# Mainboard.net
KiCad netlist of a schematic drawn in Altium Designer
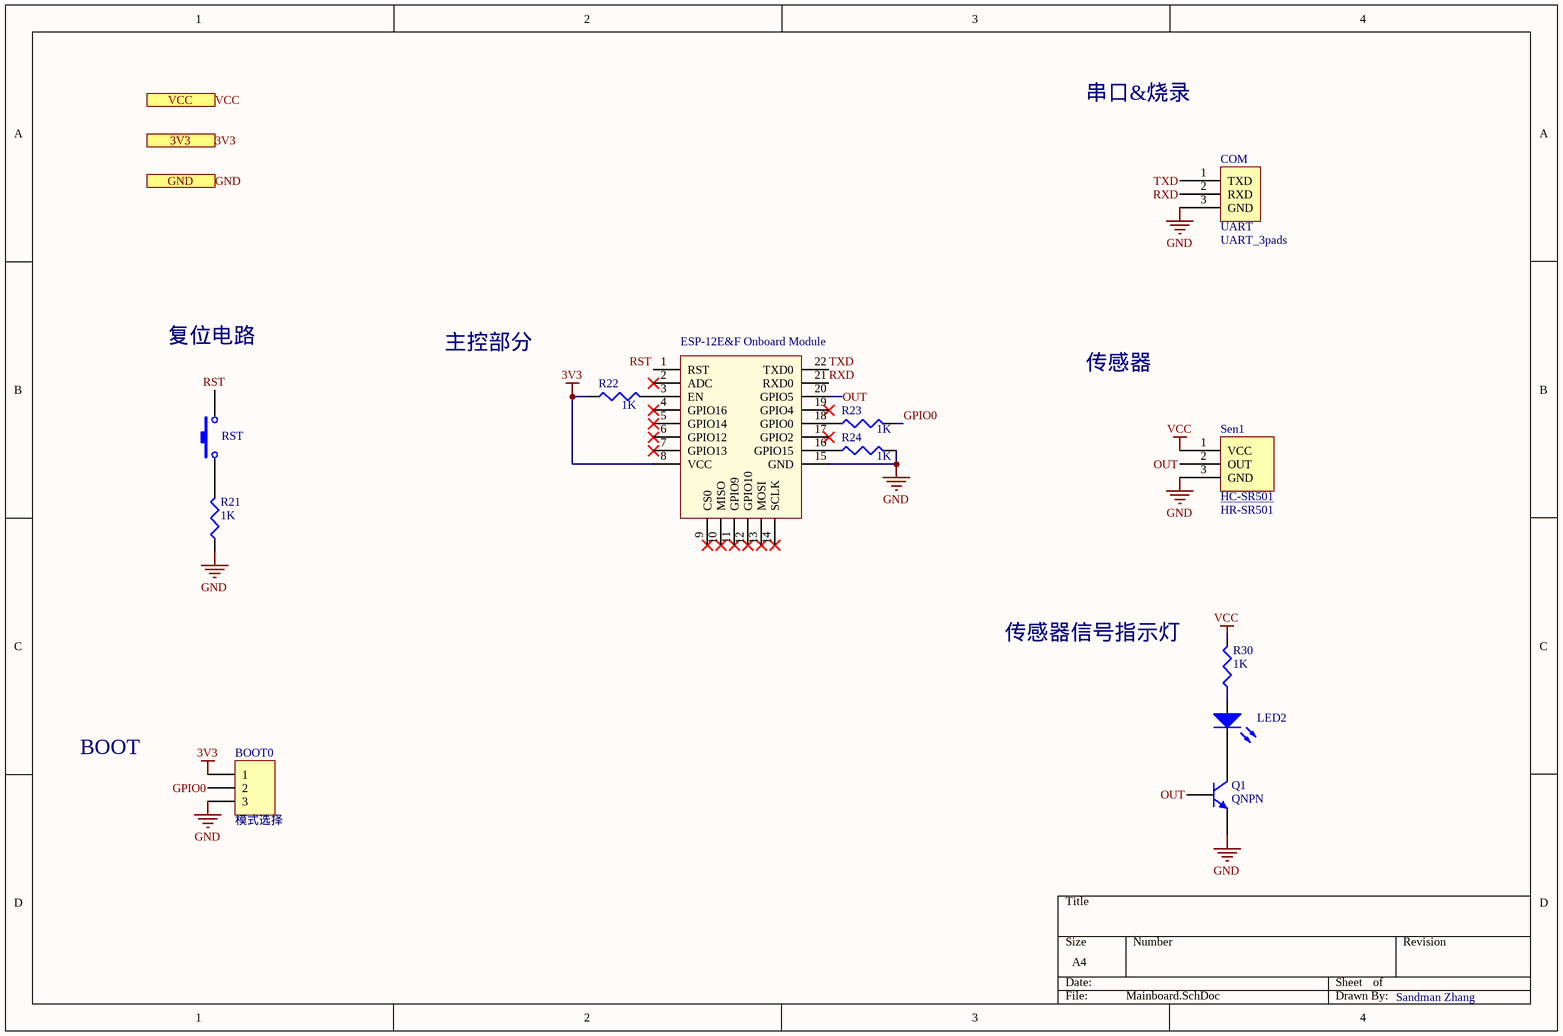
[diagram p0: Mainboard.SchDoc]

(export (version "E")
  (design (tool "Eeschema 10.0.6"))
  (components
    (comp (ref "BOOT0")
      (value "模式选择")
      (footprint "HDR1X3")
      (description "Header, 3-Pin")
      (fields (field (name "PUBLISHER") "Altium Limited"))
      (libsource (lib "Miscellaneous Connectors") (part "Header 3"))
    )
    (comp (ref "COM")
      (value "UART_3pads")
      (footprint "3pads")
      (libsource (lib "Connectivity_pads") (part "UART_3pads"))
    )
    (comp (ref "LED2")
      (value "LED3")
      (footprint "Miscellaneous Devices:6-0805_N")
      (description "Typical BLUE SiC LED")
      (fields (field (name "PUBLISHER") "Altium Limited"))
      (libsource (lib "Miscellaneous Devices") (part "LED3"))
    )
    (comp (ref "Q1")
      (value "QNPN")
      (footprint "SOT-23B_N")
      (description "NPN Bipolar Transistor")
      (fields (field (name "PUBLISHER") "Altium Limited"))
      (libsource (lib "Miscellaneous Devices") (part "QNPN"))
    )
    (comp (ref "R21")
      (value "1K")
      (footprint "J1-0603")
      (description "Resistor")
      (fields (field (name "Comment") "Res3") (field (name "PUBLISHER") "Altium Limited"))
      (libsource (lib "Miscellaneous Devices") (part "Res3"))
    )
    (comp (ref "R22")
      (value "1K")
      (footprint "J1-0603")
      (description "Resistor")
      (fields (field (name "Comment") "Res3") (field (name "PUBLISHER") "Altium Limited"))
      (libsource (lib "Miscellaneous Devices") (part "Res3"))
    )
    (comp (ref "R23")
      (value "1K")
      (footprint "J1-0603")
      (description "Resistor")
      (fields (field (name "Comment") "Res3") (field (name "PUBLISHER") "Altium Limited"))
      (libsource (lib "Miscellaneous Devices") (part "Res3"))
    )
    (comp (ref "R24")
      (value "1K")
      (footprint "J1-0603")
      (description "Resistor")
      (fields (field (name "Comment") "Res3") (field (name "PUBLISHER") "Altium Limited"))
      (libsource (lib "Miscellaneous Devices") (part "Res3"))
    )
    (comp (ref "R30")
      (value "1K")
      (footprint "6-0805_N")
      (description "Resistor")
      (fields (field (name "Comment") "Res3") (field (name "PUBLISHER") "Altium Limited"))
      (libsource (lib "Miscellaneous Devices") (part "Res3"))
    )
    (comp (ref "RST")
      (value "SW-PB")
      (footprint "SPST-2")
      (description "Switch")
      (fields (field (name "PUBLISHER") "Altium Limited"))
      (libsource (lib "Miscellaneous Devices") (part "SW-PB"))
    )
    (comp (ref "Sen1")
      (value "HR-SR501")
      (footprint "HR-SR501")
      (description "人体红外感应模块")
      (libsource (lib "Common_Modules") (part "HR-SR501"))
    )
    (comp (ref "U1")
      (value "ESP-12E&F Onboard Module")
      (footprint "ESP-12E&F Module")
      (libsource (lib "ESP-12E&F Onboard Module") (part "ESP-12E&F Onboard Module"))
    )
  )
  (nets
    (net (code "1") (name "/GPIO0") (class "Default")
      (node (ref "BOOT0") (pin "2") (pinfunction "2_2") (pintype "passive"))
      (node (ref "R23") (pin "2") (pinfunction "2_2") (pintype "passive"))
    )
    (net (code "2") (name "/OUT") (class "Default")
      (node (ref "Q1") (pin "2") (pinfunction "B_2") (pintype "passive"))
      (node (ref "Sen1") (pin "2") (pinfunction "OUT_2") (pintype "passive"))
      (node (ref "U1") (pin "20") (pinfunction "GPIO5_20") (pintype "passive"))
    )
    (net (code "3") (name "/RST") (class "Default")
      (node (ref "RST") (pin "2") (pinfunction "2_2") (pintype "passive"))
      (node (ref "U1") (pin "1") (pinfunction "RST_1") (pintype "passive"))
    )
    (net (code "4") (name "/RXD") (class "Default")
      (node (ref "COM") (pin "2") (pinfunction "RXD_2") (pintype "passive"))
      (node (ref "U1") (pin "21") (pinfunction "RXD0_21") (pintype "passive"))
    )
    (net (code "5") (name "/TXD") (class "Default")
      (node (ref "COM") (pin "1") (pinfunction "TXD_1") (pintype "passive"))
      (node (ref "U1") (pin "22") (pinfunction "TXD0_22") (pintype "passive"))
    )
    (net (code "6") (name "3V3") (class "Default")
      (node (ref "BOOT0") (pin "1") (pinfunction "1_1") (pintype "passive"))
      (node (ref "R22") (pin "1") (pinfunction "1_1") (pintype "passive"))
      (node (ref "U1") (pin "8") (pinfunction "VCC_8") (pintype "passive"))
    )
    (net (code "7") (name "GND") (class "Default")
      (node (ref "BOOT0") (pin "3") (pinfunction "3_3") (pintype "passive"))
      (node (ref "COM") (pin "3") (pinfunction "GND_3") (pintype "passive"))
      (node (ref "Q1") (pin "3") (pinfunction "E_3") (pintype "passive"))
      (node (ref "R21") (pin "1") (pinfunction "1_1") (pintype "passive"))
      (node (ref "R24") (pin "2") (pinfunction "2_2") (pintype "passive"))
      (node (ref "Sen1") (pin "3") (pinfunction "GND_3") (pintype "passive"))
      (node (ref "U1") (pin "15") (pinfunction "GND_15") (pintype "passive"))
    )
    (net (code "8") (name "Net-(LED2-A)") (class "Default")
      (node (ref "LED2") (pin "1") (pinfunction "A_1") (pintype "passive"))
      (node (ref "R30") (pin "1") (pinfunction "1_1") (pintype "passive"))
    )
    (net (code "9") (name "Net-(LED2-K)") (class "Default")
      (node (ref "LED2") (pin "2") (pinfunction "K_2") (pintype "passive"))
      (node (ref "Q1") (pin "1") (pinfunction "C_1") (pintype "passive"))
    )
    (net (code "10") (name "Net-(R21-Pad2)") (class "Default")
      (node (ref "R21") (pin "2") (pinfunction "2_2") (pintype "passive"))
      (node (ref "RST") (pin "1") (pinfunction "1_1") (pintype "passive"))
    )
    (net (code "11") (name "Net-(U1-EN)") (class "Default")
      (node (ref "R22") (pin "2") (pinfunction "2_2") (pintype "passive"))
      (node (ref "U1") (pin "3") (pinfunction "EN_3") (pintype "passive"))
    )
    (net (code "12") (name "Net-(U1-GPIO0)") (class "Default")
      (node (ref "R23") (pin "1") (pinfunction "1_1") (pintype "passive"))
      (node (ref "U1") (pin "18") (pinfunction "GPIO0_18") (pintype "passive"))
    )
    (net (code "13") (name "Net-(U1-GPIO15)") (class "Default")
      (node (ref "R24") (pin "1") (pinfunction "1_1") (pintype "passive"))
      (node (ref "U1") (pin "16") (pinfunction "GPIO15_16") (pintype "passive"))
    )
    (net (code "14") (name "VCC") (class "Default")
      (node (ref "R30") (pin "2") (pinfunction "2_2") (pintype "passive"))
      (node (ref "Sen1") (pin "1") (pinfunction "VCC_1") (pintype "passive"))
    )
    (net (code "15") (name "unconnected-(U1-ADC-Pad2)") (class "Default")
      (node (ref "U1") (pin "2") (pinfunction "ADC_2") (pintype "passive+no_connect"))
    )
    (net (code "16") (name "unconnected-(U1-CS0-Pad9)") (class "Default")
      (node (ref "U1") (pin "9") (pinfunction "CS0_9") (pintype "passive+no_connect"))
    )
    (net (code "17") (name "unconnected-(U1-GPIO2-Pad17)") (class "Default")
      (node (ref "U1") (pin "17") (pinfunction "GPIO2_17") (pintype "passive+no_connect"))
    )
    (net (code "18") (name "unconnected-(U1-GPIO4-Pad19)") (class "Default")
      (node (ref "U1") (pin "19") (pinfunction "GPIO4_19") (pintype "passive+no_connect"))
    )
    (net (code "19") (name "unconnected-(U1-GPIO9-Pad11)") (class "Default")
      (node (ref "U1") (pin "11") (pinfunction "GPIO9_11") (pintype "passive+no_connect"))
    )
    (net (code "20") (name "unconnected-(U1-GPIO10-Pad12)") (class "Default")
      (node (ref "U1") (pin "12") (pinfunction "GPIO10_12") (pintype "passive+no_connect"))
    )
    (net (code "21") (name "unconnected-(U1-GPIO12-Pad6)") (class "Default")
      (node (ref "U1") (pin "6") (pinfunction "GPIO12_6") (pintype "passive+no_connect"))
    )
    (net (code "22") (name "unconnected-(U1-GPIO13-Pad7)") (class "Default")
      (node (ref "U1") (pin "7") (pinfunction "GPIO13_7") (pintype "passive+no_connect"))
    )
    (net (code "23") (name "unconnected-(U1-GPIO14-Pad5)") (class "Default")
      (node (ref "U1") (pin "5") (pinfunction "GPIO14_5") (pintype "passive+no_connect"))
    )
    (net (code "24") (name "unconnected-(U1-GPIO16-Pad4)") (class "Default")
      (node (ref "U1") (pin "4") (pinfunction "GPIO16_4") (pintype "passive+no_connect"))
    )
    (net (code "25") (name "unconnected-(U1-MISO-Pad10)") (class "Default")
      (node (ref "U1") (pin "10") (pinfunction "MISO_10") (pintype "passive+no_connect"))
    )
    (net (code "26") (name "unconnected-(U1-MOSI-Pad13)") (class "Default")
      (node (ref "U1") (pin "13") (pinfunction "MOSI_13") (pintype "passive+no_connect"))
    )
    (net (code "27") (name "unconnected-(U1-SCLK-Pad14)") (class "Default")
      (node (ref "U1") (pin "14") (pinfunction "SCLK_14") (pintype "passive+no_connect"))
    )
  )
)
